# Lab7-8_CH1.net
KiCad netlist of a schematic drawn in Altium Designer
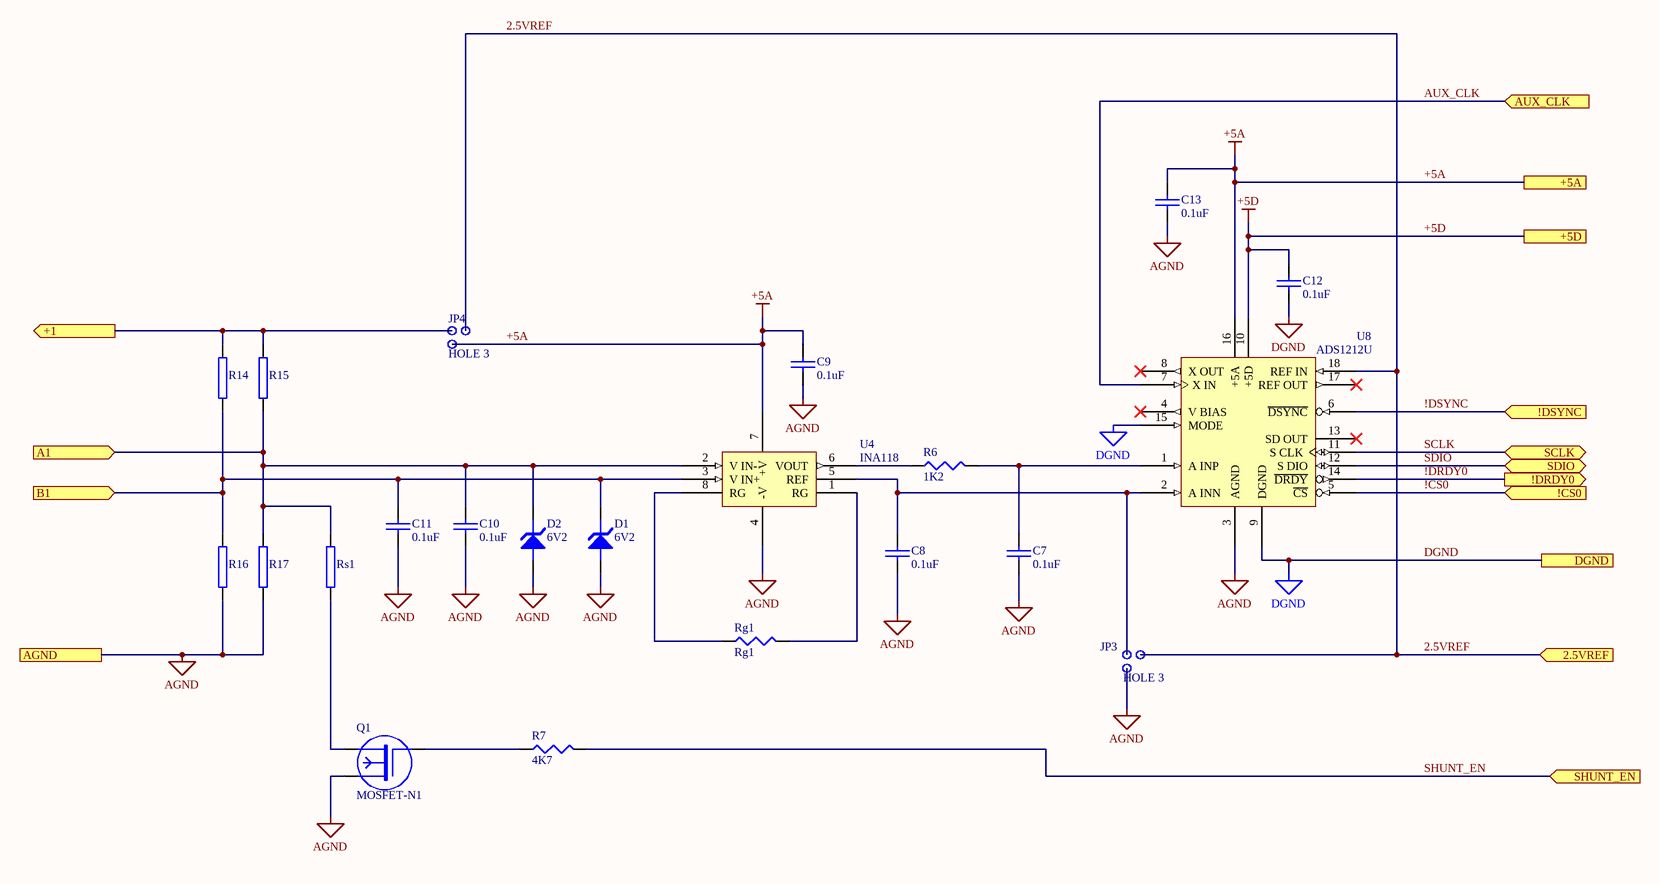
[diagram p0: Lab7-8_CH1.SchDoc]

(export (version "E")
  (design (tool "Eeschema 10.0.6"))
  (components
    (comp (ref "C7")
      (value "0.1uF")
      (footprint "0805")
      (libsource (lib "ECET231_ProjectThree_SCHLIB_Rev02") (part "CAP"))
    )
    (comp (ref "C8")
      (value "0.1uF")
      (footprint "0805")
      (libsource (lib "ECET231_ProjectThree_SCHLIB_Rev02") (part "CAP"))
    )
    (comp (ref "C9")
      (value "0.1uF")
      (footprint "0805")
      (libsource (lib "ECET231_ProjectThree_SCHLIB_Rev02") (part "CAP"))
    )
    (comp (ref "C10")
      (value "0.1uF")
      (footprint "0805")
      (libsource (lib "ECET231_ProjectThree_SCHLIB_Rev02") (part "CAP"))
    )
    (comp (ref "C11")
      (value "0.1uF")
      (footprint "0805")
      (libsource (lib "ECET231_ProjectThree_SCHLIB_Rev02") (part "CAP"))
    )
    (comp (ref "C12")
      (value "0.1uF")
      (footprint "0805")
      (libsource (lib "ECET231_ProjectThree_SCHLIB_Rev02") (part "CAP"))
    )
    (comp (ref "C13")
      (value "0.1uF")
      (footprint "0805")
      (libsource (lib "ECET231_ProjectThree_SCHLIB_Rev02") (part "CAP"))
    )
    (comp (ref "D1")
      (value "6V2")
      (footprint "SOD-123")
      (libsource (lib "ECET231_ProjectThree_SCHLIB_Rev02") (part "ZENER3"))
    )
    (comp (ref "D2")
      (value "6V2")
      (footprint "SOD-123")
      (libsource (lib "ECET231_ProjectThree_SCHLIB_Rev02") (part "ZENER3"))
    )
    (comp (ref "JP3")
      (value "HOLE 3")
      (footprint "RAD0.1A")
      (libsource (lib "ECET231_ProjectThree_SCHLIB_Rev02") (part "HOLE 3"))
    )
    (comp (ref "JP4")
      (value "HOLE 3")
      (footprint "RAD0.1A")
      (libsource (lib "ECET231_ProjectThree_SCHLIB_Rev02") (part "HOLE 3"))
    )
    (comp (ref "Q1")
      (value "MOSFET-N1")
      (footprint "SOT-23")
      (libsource (lib "ECET231_ProjectThree_SCHLIB_Rev02") (part "MOSFET-N1"))
    )
    (comp (ref "R6")
      (value "1K2")
      (footprint "0805")
      (libsource (lib "ECET231_ProjectThree_SCHLIB_Rev02") (part "RES1"))
    )
    (comp (ref "R7")
      (value "4K7")
      (footprint "0805")
      (libsource (lib "ECET231_ProjectThree_SCHLIB_Rev02") (part "RES1"))
    )
    (comp (ref "R14")
      (value "bridge R")
      (footprint "bridge resistor")
      (libsource (lib "ECET231_ProjectThree_SCHLIB_Rev02") (part "RES2"))
    )
    (comp (ref "R15")
      (value "bridge R")
      (footprint "bridge resistor")
      (libsource (lib "ECET231_ProjectThree_SCHLIB_Rev02") (part "RES2"))
    )
    (comp (ref "R16")
      (value "bridge R")
      (footprint "bridge resistor")
      (libsource (lib "ECET231_ProjectThree_SCHLIB_Rev02") (part "RES2"))
    )
    (comp (ref "R17")
      (value "bridge R")
      (footprint "bridge resistor")
      (libsource (lib "ECET231_ProjectThree_SCHLIB_Rev02") (part "RES2"))
    )
    (comp (ref "Rg1")
      (value "Rg1")
      (footprint "0805")
      (libsource (lib "ECET231_ProjectThree_SCHLIB_Rev02") (part "RES1"))
    )
    (comp (ref "Rs1")
      (value "bridge R")
      (footprint "bridge resistor")
      (libsource (lib "ECET231_ProjectThree_SCHLIB_Rev02") (part "RES2"))
    )
    (comp (ref "U4")
      (value "INA118")
      (footprint "SO-8")
      (description "Precision, Low Power Instrumentation Amplifier")
      (libsource (lib "ECET231_ProjectThree_SCHLIB_Rev02") (part "INA118"))
    )
    (comp (ref "U8")
      (value "ADS1212U")
      (footprint "SOIC18")
      (description "22-Bit Analog-to-Digital Converter")
      (libsource (lib "ECET231_ProjectThree_SCHLIB_Rev02") (part "ADS1212U(18)"))
    )
  )
  (nets
    (net (code "1") (name "+5A") (class "Default")
      (node (ref "C13") (pin "1") (pintype "passive"))
      (node (ref "C9") (pin "1") (pintype "passive"))
      (node (ref "JP4") (pin "1") (pinfunction "1_1") (pintype "passive"))
      (node (ref "U4") (pin "7") (pinfunction "+V_7") (pintype "power_in"))
      (node (ref "U8") (pin "16") (pinfunction "+5A_16") (pintype "power_in"))
    )
    (net (code "2") (name "+5D") (class "Default")
      (node (ref "C12") (pin "1") (pintype "passive"))
      (node (ref "U8") (pin "10") (pinfunction "+5D_10") (pintype "power_in"))
    )
    (net (code "3") (name "/!CS0") (class "Default")
      (node (ref "U8") (pin "5") (pinfunction "~{CS}_5") (pintype "input"))
    )
    (net (code "4") (name "/!DRDY0") (class "Default")
      (node (ref "U8") (pin "14") (pinfunction "~{DRDY}_14") (pintype "output"))
    )
    (net (code "5") (name "/!DSYNC") (class "Default")
      (node (ref "U8") (pin "6") (pinfunction "~{DSYNC}_6") (pintype "input"))
    )
    (net (code "6") (name "/+1") (class "Default")
      (node (ref "JP4") (pin "2") (pinfunction "2_2") (pintype "passive"))
      (node (ref "R14") (pin "2") (pintype "passive"))
      (node (ref "R15") (pin "2") (pintype "passive"))
    )
    (net (code "7") (name "/2.5VREF") (class "Default")
      (node (ref "JP3") (pin "3") (pinfunction "3_3") (pintype "passive"))
      (node (ref "JP4") (pin "3") (pinfunction "3_3") (pintype "passive"))
      (node (ref "U8") (pin "18") (pinfunction "REF_IN_18") (pintype "input"))
    )
    (net (code "8") (name "/A1") (class "Default")
      (node (ref "C10") (pin "1") (pintype "passive"))
      (node (ref "D2") (pin "K") (pintype "passive"))
      (node (ref "R15") (pin "1") (pintype "passive"))
      (node (ref "R17") (pin "2") (pintype "passive"))
      (node (ref "Rs1") (pin "2") (pintype "passive"))
      (node (ref "U4") (pin "2") (pinfunction "V_IN-_2") (pintype "input"))
    )
    (net (code "9") (name "/AUX_CLK") (class "Default")
      (node (ref "U8") (pin "7") (pinfunction "X_IN_7") (pintype "input"))
    )
    (net (code "10") (name "/B1") (class "Default")
      (node (ref "C11") (pin "1") (pintype "passive"))
      (node (ref "D1") (pin "K") (pintype "passive"))
      (node (ref "R14") (pin "1") (pintype "passive"))
      (node (ref "R16") (pin "2") (pintype "passive"))
      (node (ref "U4") (pin "3") (pinfunction "V_IN+_3") (pintype "input"))
    )
    (net (code "11") (name "/SCLK") (class "Default")
      (node (ref "U8") (pin "11") (pinfunction "S_CLK_11") (pintype "bidirectional"))
    )
    (net (code "12") (name "/SDIO") (class "Default")
      (node (ref "U8") (pin "12") (pinfunction "S_DIO_12") (pintype "bidirectional"))
    )
    (net (code "13") (name "/SHUNT_EN") (class "Default") (node (ref "R7") (pin "2") (pintype "passive")))
    (net (code "14") (name "AGND") (class "Default")
      (node (ref "C10") (pin "2") (pintype "passive"))
      (node (ref "C11") (pin "2") (pintype "passive"))
      (node (ref "C13") (pin "2") (pintype "passive"))
      (node (ref "C7") (pin "2") (pintype "passive"))
      (node (ref "C8") (pin "2") (pintype "passive"))
      (node (ref "C9") (pin "2") (pintype "passive"))
      (node (ref "D1") (pin "A") (pintype "passive"))
      (node (ref "D2") (pin "A") (pintype "passive"))
      (node (ref "JP3") (pin "1") (pinfunction "1_1") (pintype "passive"))
      (node (ref "Q1") (pin "2") (pintype "passive"))
      (node (ref "R16") (pin "1") (pintype "passive"))
      (node (ref "R17") (pin "1") (pintype "passive"))
      (node (ref "U4") (pin "4") (pinfunction "-V_4") (pintype "power_in"))
      (node (ref "U8") (pin "3") (pinfunction "AGND_3") (pintype "power_in"))
    )
    (net (code "15") (name "DGND") (class "Default")
      (node (ref "C12") (pin "2") (pintype "passive"))
      (node (ref "U8") (pin "15") (pinfunction "MODE_15") (pintype "input"))
      (node (ref "U8") (pin "9") (pinfunction "DGND_9") (pintype "power_in"))
    )
    (net (code "16") (name "Net-(Q1-Pad1)") (class "Default")
      (node (ref "Q1") (pin "1") (pintype "passive"))
      (node (ref "R7") (pin "1") (pintype "passive"))
    )
    (net (code "17") (name "Net-(Q1-Pad3)") (class "Default")
      (node (ref "Q1") (pin "3") (pintype "passive"))
      (node (ref "Rs1") (pin "1") (pintype "passive"))
    )
    (net (code "18") (name "Net-(Rg1-Pad1)") (class "Default")
      (node (ref "Rg1") (pin "1") (pintype "passive"))
      (node (ref "U4") (pin "8") (pinfunction "RG_8") (pintype "passive"))
    )
    (net (code "19") (name "Net-(Rg1-Pad2)") (class "Default")
      (node (ref "Rg1") (pin "2") (pintype "passive"))
      (node (ref "U4") (pin "1") (pinfunction "RG_1") (pintype "passive"))
    )
    (net (code "20") (name "Net-(U4-REF)") (class "Default")
      (node (ref "C8") (pin "1") (pintype "passive"))
      (node (ref "JP3") (pin "2") (pinfunction "2_2") (pintype "passive"))
      (node (ref "U4") (pin "5") (pinfunction "REF_5") (pintype "passive"))
      (node (ref "U8") (pin "2") (pinfunction "A_INN_2") (pintype "input"))
    )
    (net (code "21") (name "Net-(U4-VOUT)") (class "Default")
      (node (ref "R6") (pin "1") (pintype "passive"))
      (node (ref "U4") (pin "6") (pinfunction "VOUT_6") (pintype "output"))
    )
    (net (code "22") (name "Net-(U8-A_INP)") (class "Default")
      (node (ref "C7") (pin "1") (pintype "passive"))
      (node (ref "R6") (pin "2") (pintype "passive"))
      (node (ref "U8") (pin "1") (pinfunction "A_INP_1") (pintype "input"))
    )
    (net (code "23") (name "unconnected-(U8-REF_OUT-Pad17)") (class "Default")
      (node (ref "U8") (pin "17") (pinfunction "REF_OUT_17") (pintype "output+no_connect"))
    )
    (net (code "24") (name "unconnected-(U8-SD_OUT-Pad13)") (class "Default")
      (node (ref "U8") (pin "13") (pinfunction "SD_OUT_13") (pintype "tri_state+no_connect"))
    )
    (net (code "25") (name "unconnected-(U8-V_BIAS-Pad4)") (class "Default")
      (node (ref "U8") (pin "4") (pinfunction "V_BIAS_4") (pintype "output+no_connect"))
    )
    (net (code "26") (name "unconnected-(U8-X_OUT-Pad8)") (class "Default")
      (node (ref "U8") (pin "8") (pinfunction "X_OUT_8") (pintype "output+no_connect"))
    )
  )
)
